# QVGA.net
KiCad netlist of a schematic drawn in Altium Designer
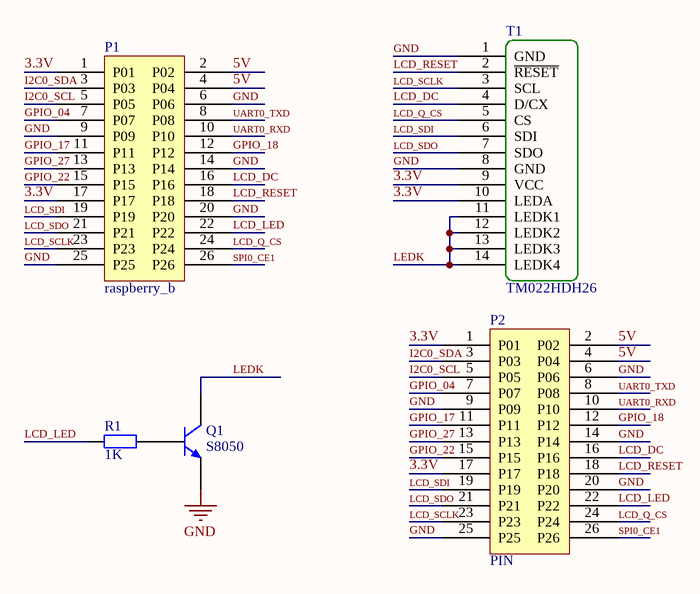
[diagram p0: QVGA.SchDoc]

(export (version "E")
  (design (tool "Eeschema 10.0.6"))
  (components
    (comp (ref "P1")
      (value "raspberry_b")
      (footprint "raspberry_b")
      (libsource (lib "2.2_TFT") (part "raspberry_b"))
    )
    (comp (ref "P2") (value "PIN") (footprint "GPIO13x2") (libsource (lib "2.2_TFT") (part "raspberry_b")))
    (comp (ref "Q1")
      (value "S8050")
      (footprint "SOT23 - duplicate")
      (libsource (lib "2.2_TFT") (part "S8050"))
    )
    (comp (ref "R1") (value "1K") (footprint "1206") (libsource (lib "2.2_TFT") (part "register")))
    (comp (ref "T1")
      (value "TM022HDH26")
      (footprint "TM022HDH26")
      (description "2.2寸无触摸")
      (libsource (lib "2.2_TFT") (part "TM022HDH26"))
    )
  )
  (nets
    (net (code "1") (name "/3.3V") (class "Default")
      (node (ref "P1") (pin "1") (pinfunction "P01_1") (pintype "passive"))
      (node (ref "P1") (pin "17") (pinfunction "P17_17") (pintype "passive"))
      (node (ref "P2") (pin "1") (pinfunction "P01_1") (pintype "passive"))
      (node (ref "P2") (pin "17") (pinfunction "P17_17") (pintype "passive"))
      (node (ref "T1") (pin "10") (pinfunction "LEDA_10") (pintype "passive"))
      (node (ref "T1") (pin "9") (pinfunction "VCC_9") (pintype "passive"))
    )
    (net (code "2") (name "/5V") (class "Default")
      (node (ref "P1") (pin "2") (pinfunction "P02_2") (pintype "passive"))
      (node (ref "P1") (pin "4") (pinfunction "P04_4") (pintype "passive"))
      (node (ref "P2") (pin "2") (pinfunction "P02_2") (pintype "passive"))
      (node (ref "P2") (pin "4") (pinfunction "P04_4") (pintype "passive"))
    )
    (net (code "3") (name "/GPIO_04") (class "Default")
      (node (ref "P1") (pin "7") (pinfunction "P07_7") (pintype "passive"))
      (node (ref "P2") (pin "7") (pinfunction "P07_7") (pintype "passive"))
    )
    (net (code "4") (name "/GPIO_17") (class "Default")
      (node (ref "P1") (pin "11") (pinfunction "P11_11") (pintype "passive"))
      (node (ref "P2") (pin "11") (pinfunction "P11_11") (pintype "passive"))
    )
    (net (code "5") (name "/GPIO_18") (class "Default")
      (node (ref "P1") (pin "12") (pinfunction "P12_12") (pintype "passive"))
      (node (ref "P2") (pin "12") (pinfunction "P12_12") (pintype "passive"))
    )
    (net (code "6") (name "/GPIO_22") (class "Default")
      (node (ref "P1") (pin "15") (pinfunction "P15_15") (pintype "passive"))
      (node (ref "P2") (pin "15") (pinfunction "P15_15") (pintype "passive"))
    )
    (net (code "7") (name "/GPIO_27") (class "Default")
      (node (ref "P1") (pin "13") (pinfunction "P13_13") (pintype "passive"))
      (node (ref "P2") (pin "13") (pinfunction "P13_13") (pintype "passive"))
    )
    (net (code "8") (name "/I2C0_SCL") (class "Default")
      (node (ref "P1") (pin "5") (pinfunction "P05_5") (pintype "passive"))
      (node (ref "P2") (pin "5") (pinfunction "P05_5") (pintype "passive"))
    )
    (net (code "9") (name "/I2C0_SDA") (class "Default")
      (node (ref "P1") (pin "3") (pinfunction "P03_3") (pintype "passive"))
      (node (ref "P2") (pin "3") (pinfunction "P03_3") (pintype "passive"))
    )
    (net (code "10") (name "/LCD_DC") (class "Default")
      (node (ref "P1") (pin "16") (pinfunction "P16_16") (pintype "passive"))
      (node (ref "P2") (pin "16") (pinfunction "P16_16") (pintype "passive"))
      (node (ref "T1") (pin "4") (pinfunction "D/CX_4") (pintype "passive"))
    )
    (net (code "11") (name "/LCD_LED") (class "Default")
      (node (ref "P1") (pin "22") (pinfunction "P22_22") (pintype "passive"))
      (node (ref "P2") (pin "22") (pinfunction "P22_22") (pintype "passive"))
      (node (ref "R1") (pin "1") (pinfunction "1_1") (pintype "passive"))
    )
    (net (code "12") (name "/LCD_Q_CS") (class "Default")
      (node (ref "P1") (pin "24") (pinfunction "P24_24") (pintype "passive"))
      (node (ref "P2") (pin "24") (pinfunction "P24_24") (pintype "passive"))
      (node (ref "T1") (pin "5") (pinfunction "CS_5") (pintype "passive"))
    )
    (net (code "13") (name "/LCD_RESET") (class "Default")
      (node (ref "P1") (pin "18") (pinfunction "P18_18") (pintype "passive"))
      (node (ref "P2") (pin "18") (pinfunction "P18_18") (pintype "passive"))
      (node (ref "T1") (pin "2") (pinfunction "~{RESET}_2") (pintype "passive"))
    )
    (net (code "14") (name "/LCD_SCLK") (class "Default")
      (node (ref "P1") (pin "23") (pinfunction "P23_23") (pintype "passive"))
      (node (ref "P2") (pin "23") (pinfunction "P23_23") (pintype "passive"))
      (node (ref "T1") (pin "3") (pinfunction "SCL_3") (pintype "passive"))
    )
    (net (code "15") (name "/LCD_SDI") (class "Default")
      (node (ref "P1") (pin "19") (pinfunction "P19_19") (pintype "passive"))
      (node (ref "P2") (pin "19") (pinfunction "P19_19") (pintype "passive"))
      (node (ref "T1") (pin "6") (pinfunction "SDI_6") (pintype "passive"))
    )
    (net (code "16") (name "/LCD_SDO") (class "Default")
      (node (ref "P1") (pin "21") (pinfunction "P21_21") (pintype "passive"))
      (node (ref "P2") (pin "21") (pinfunction "P21_21") (pintype "passive"))
      (node (ref "T1") (pin "7") (pinfunction "SDO_7") (pintype "passive"))
    )
    (net (code "17") (name "/LEDK") (class "Default")
      (node (ref "Q1") (pin "3") (pinfunction "C_3") (pintype "passive"))
      (node (ref "T1") (pin "11") (pinfunction "LEDK1_11") (pintype "passive"))
      (node (ref "T1") (pin "12") (pinfunction "LEDK2_12") (pintype "passive"))
      (node (ref "T1") (pin "13") (pinfunction "LEDK3_13") (pintype "passive"))
      (node (ref "T1") (pin "14") (pinfunction "LEDK4_14") (pintype "passive"))
    )
    (net (code "18") (name "/SPI0_CE1") (class "Default")
      (node (ref "P1") (pin "26") (pinfunction "P26_26") (pintype "passive"))
      (node (ref "P2") (pin "26") (pinfunction "P26_26") (pintype "passive"))
    )
    (net (code "19") (name "/UART0_RXD") (class "Default")
      (node (ref "P1") (pin "10") (pinfunction "P10_10") (pintype "passive"))
      (node (ref "P2") (pin "10") (pinfunction "P10_10") (pintype "passive"))
    )
    (net (code "20") (name "/UART0_TXD") (class "Default")
      (node (ref "P1") (pin "8") (pinfunction "P08_8") (pintype "passive"))
      (node (ref "P2") (pin "8") (pinfunction "P08_8") (pintype "passive"))
    )
    (net (code "21") (name "GND") (class "Default")
      (node (ref "P1") (pin "14") (pinfunction "P14_14") (pintype "passive"))
      (node (ref "P1") (pin "20") (pinfunction "P20_20") (pintype "passive"))
      (node (ref "P1") (pin "25") (pinfunction "P25_25") (pintype "passive"))
      (node (ref "P1") (pin "6") (pinfunction "P06_6") (pintype "passive"))
      (node (ref "P1") (pin "9") (pinfunction "P09_9") (pintype "passive"))
      (node (ref "P2") (pin "14") (pinfunction "P14_14") (pintype "passive"))
      (node (ref "P2") (pin "20") (pinfunction "P20_20") (pintype "passive"))
      (node (ref "P2") (pin "25") (pinfunction "P25_25") (pintype "passive"))
      (node (ref "P2") (pin "6") (pinfunction "P06_6") (pintype "passive"))
      (node (ref "P2") (pin "9") (pinfunction "P09_9") (pintype "passive"))
      (node (ref "Q1") (pin "1") (pinfunction "E_1") (pintype "passive"))
      (node (ref "T1") (pin "1") (pinfunction "GND_1") (pintype "passive"))
      (node (ref "T1") (pin "8") (pinfunction "GND_8") (pintype "passive"))
    )
    (net (code "22") (name "Net-(Q1-B)") (class "Default")
      (node (ref "Q1") (pin "2") (pinfunction "B_2") (pintype "passive"))
      (node (ref "R1") (pin "2") (pinfunction "2_2") (pintype "passive"))
    )
  )
)
